# LPC1768HeaderBoardV1_0Sch.net
KiCad netlist of a schematic drawn in Altium Designer
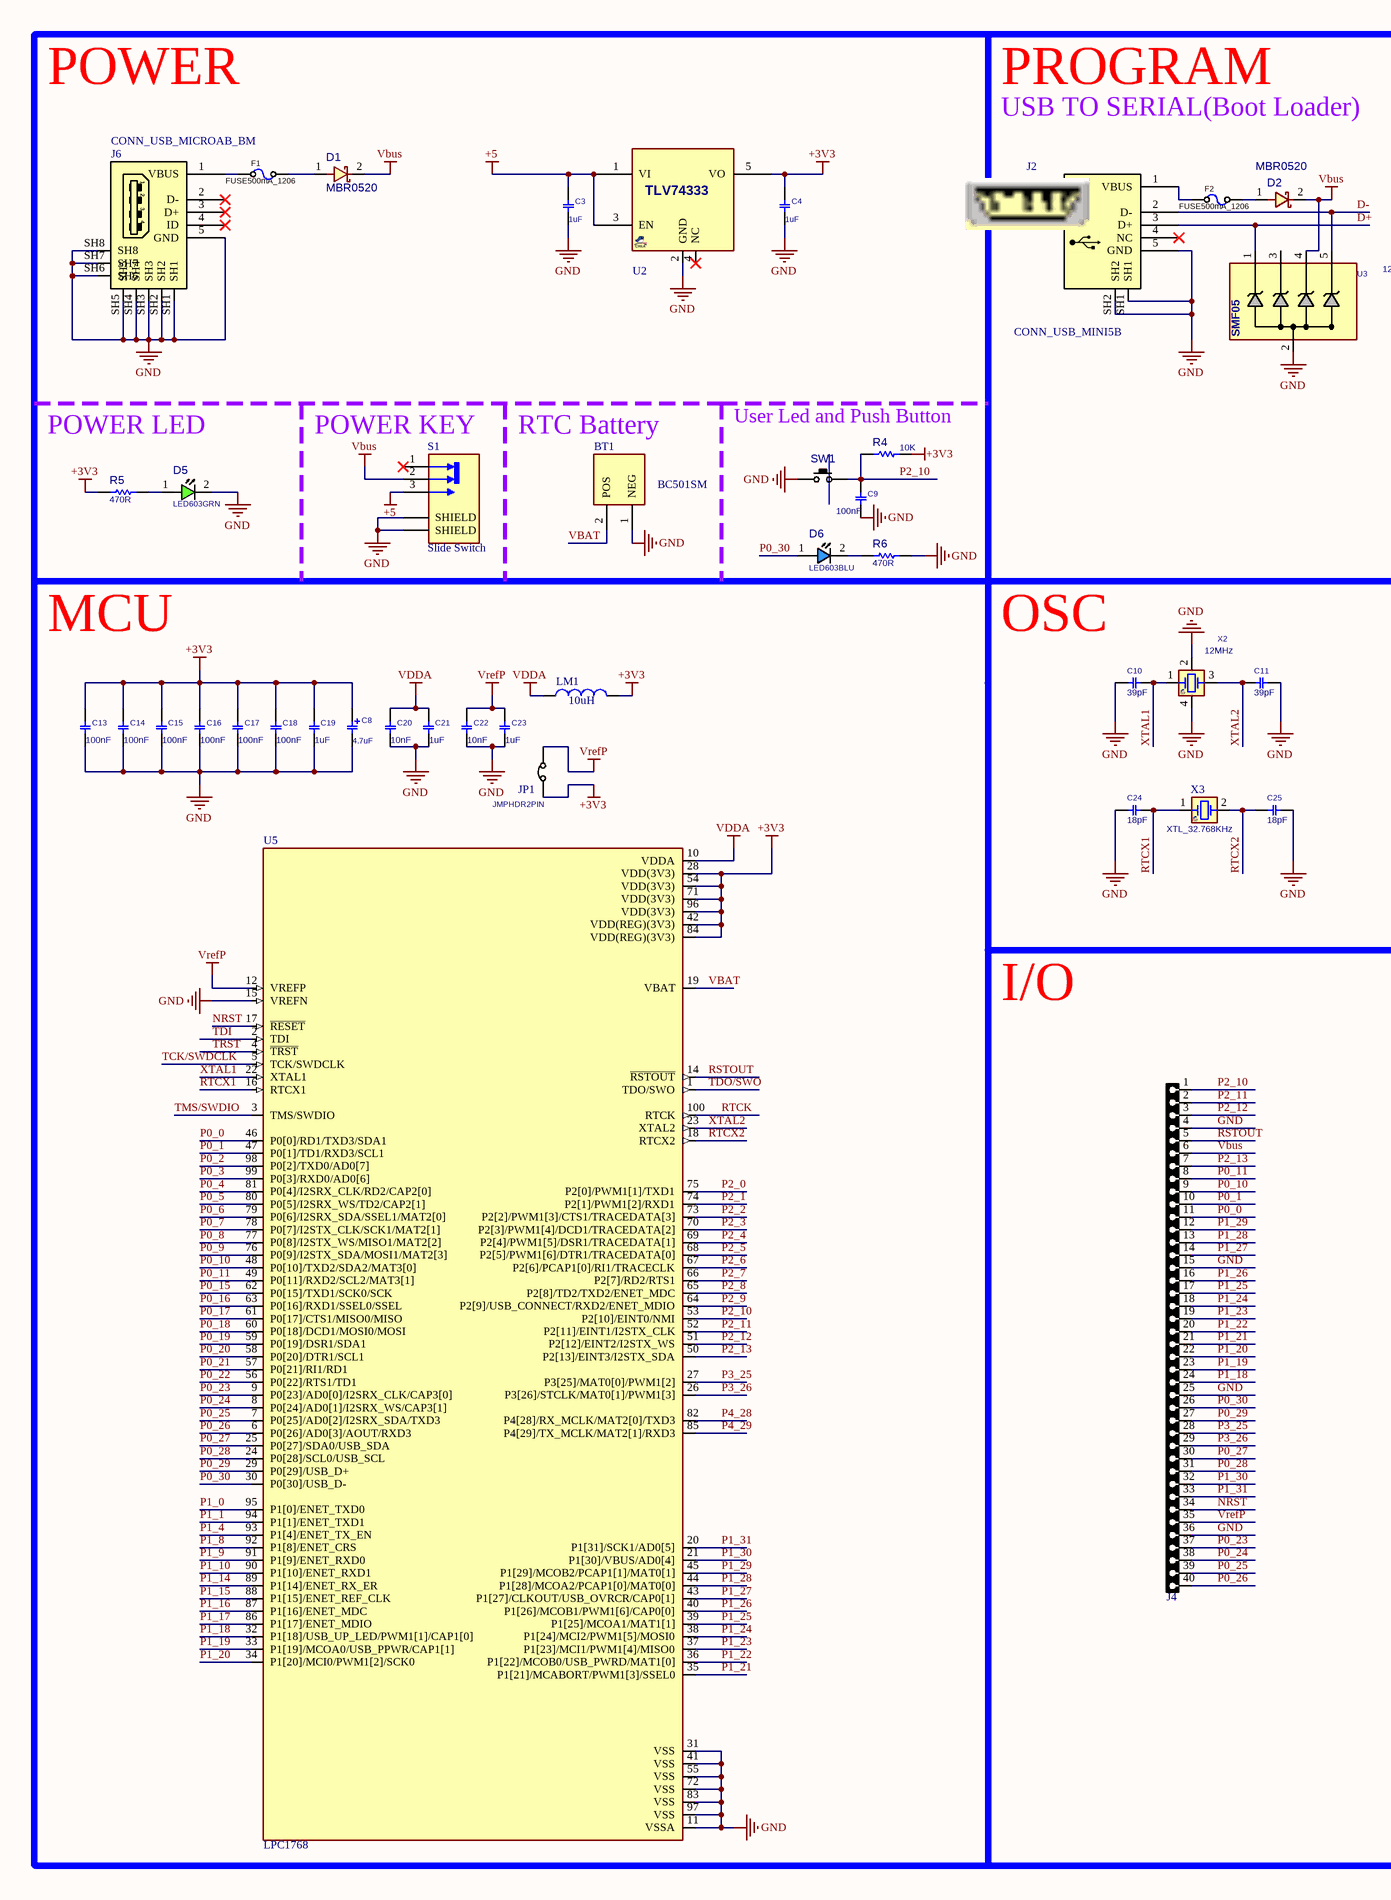
[diagram p0: LPC1768HeaderBoardV1.0Sch.SchDoc, left]
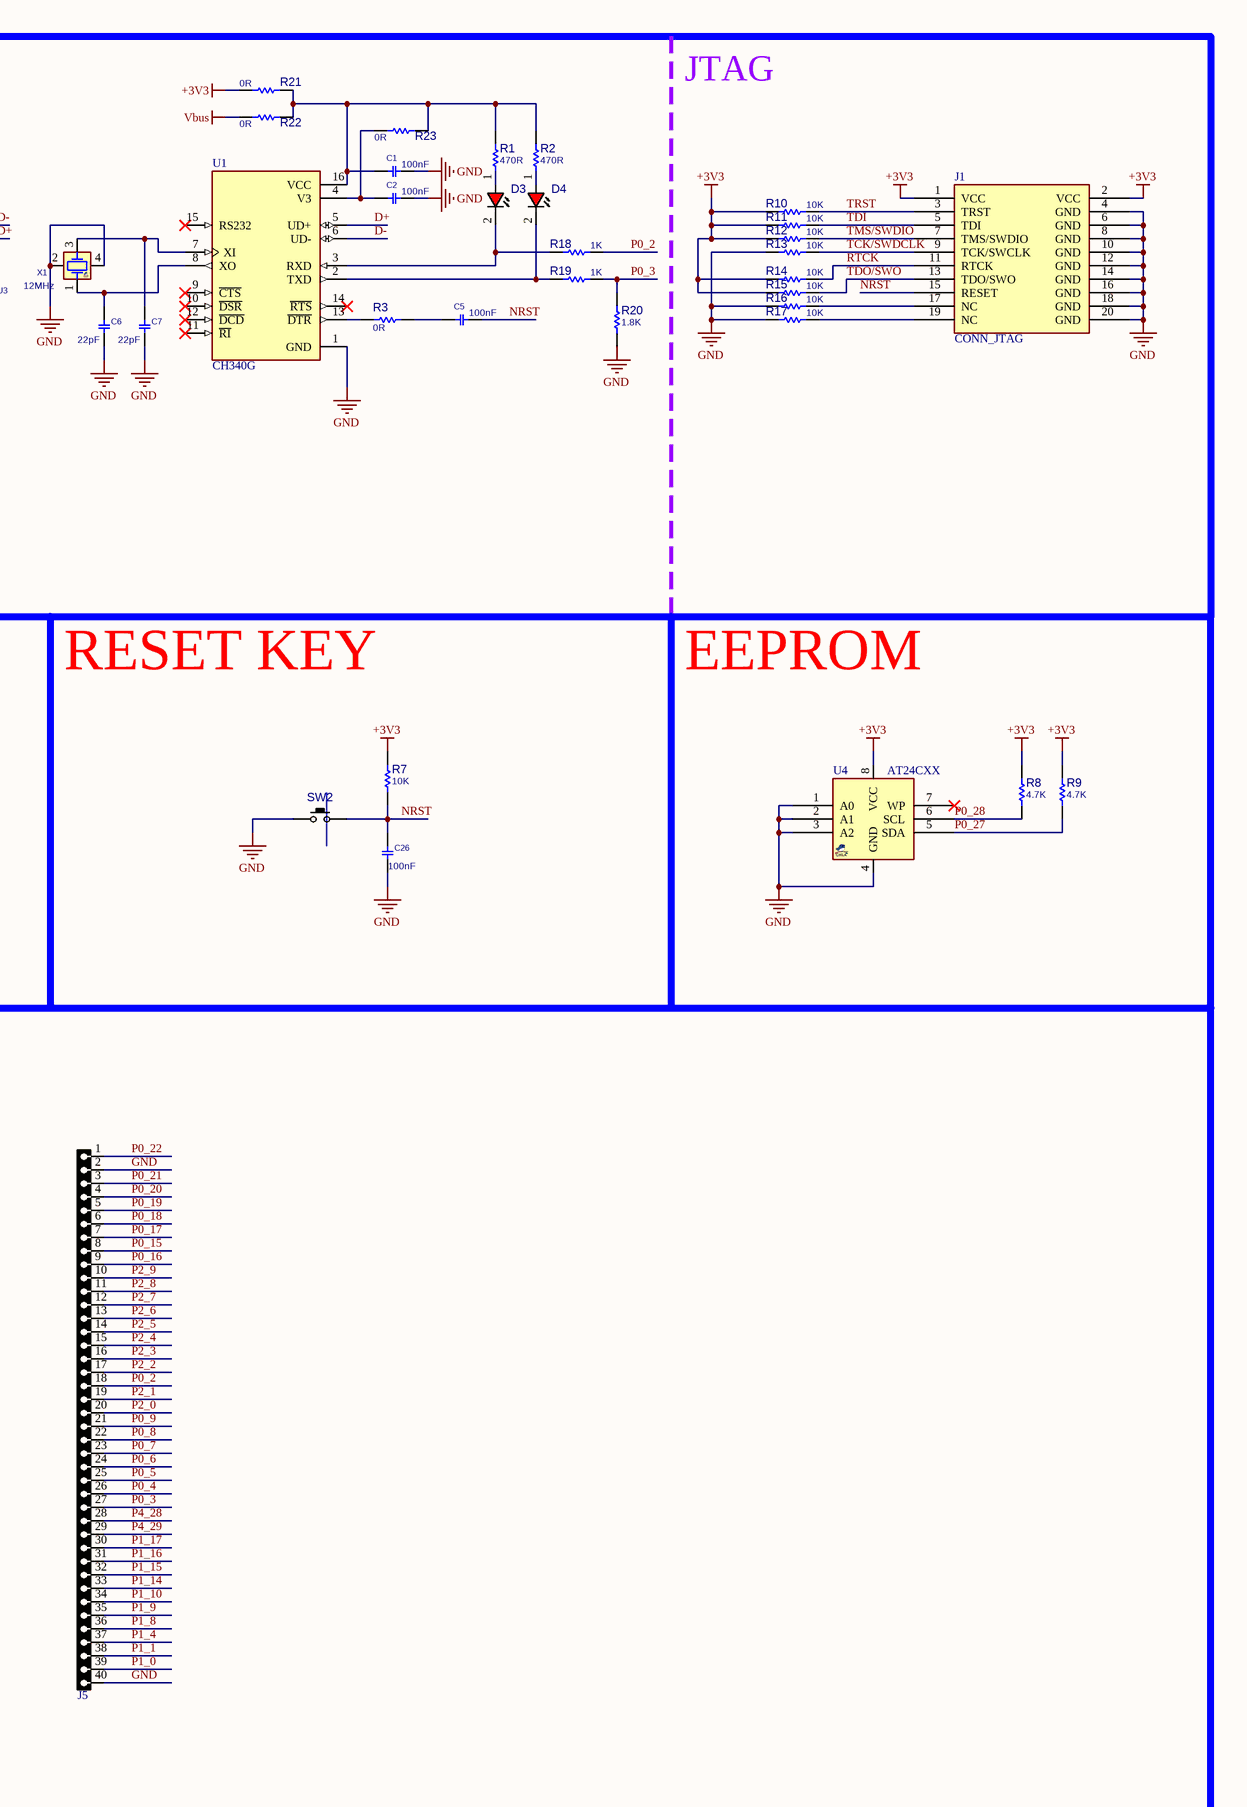
[diagram p1: LPC1768HeaderBoardV1.0Sch.SchDoc, right]

(export (version "E")
  (design (tool "Eeschema 10.0.6"))
  (components
    (comp (ref "BT1") (value "BC501SM") (footprint "BC501SM") (libsource (lib "Mehrdad") (part "BC501SM")))
    (comp (ref "C1")
      (value "100nF")
      (footprint "C0603")
      (description "CAP, MLCC")
      (fields (field (name "MANF_P#") "MANF_PART#"))
      (libsource (lib "passive_smd") (part "CAP_SMD_MLCC_0603"))
    )
    (comp (ref "C2")
      (value "100nF")
      (footprint "C0603")
      (description "CAP, MLCC")
      (fields (field (name "MANF_P#") "MANF_PART#"))
      (libsource (lib "passive_smd") (part "CAP_SMD_MLCC_0603"))
    )
    (comp (ref "C3")
      (value "1uF")
      (footprint "C0805")
      (description "CAP, MLCC, -F, -V, MATERIAL, -%, 0201")
      (fields (field (name "MANF_P#") "MANF_PART#"))
      (libsource (lib "passive_smd") (part "CAP_SMD_MLCC_0805"))
    )
    (comp (ref "C4")
      (value "1uF")
      (footprint "C0805")
      (description "CAP, MLCC, -F, -V, MATERIAL, -%, 0201")
      (fields (field (name "MANF_P#") "MANF_PART#"))
      (libsource (lib "passive_smd") (part "CAP_SMD_MLCC_0805"))
    )
    (comp (ref "C5")
      (value "100nF")
      (footprint "C0603")
      (description "CAP, MLCC")
      (fields (field (name "MANF_P#") "MANF_PART#"))
      (libsource (lib "passive_smd") (part "CAP_SMD_MLCC_0603"))
    )
    (comp (ref "C6")
      (value "22pF")
      (footprint "C0603")
      (description "CAP, MLCC")
      (fields (field (name "MANF_P#") "MANF_PART#"))
      (libsource (lib "passive_smd") (part "CAP_SMD_MLCC_0603"))
    )
    (comp (ref "C7")
      (value "22pF")
      (footprint "C0603")
      (description "CAP, MLCC")
      (fields (field (name "MANF_P#") "MANF_PART#"))
      (libsource (lib "passive_smd") (part "CAP_SMD_MLCC_0603"))
    )
    (comp (ref "C8")
      (value "4.7uF")
      (footprint "C_TN_3216")
      (description "CAP, SMD, TAN,")
      (libsource (lib "passive_smd") (part "CAP_SMD_TAN_3216"))
    )
    (comp (ref "C9")
      (value "100nF")
      (footprint "C0603")
      (description "CAP, MLCC")
      (fields (field (name "MANF_P#") "MANF_PART#"))
      (libsource (lib "passive_smd") (part "CAP_SMD_MLCC_0603"))
    )
    (comp (ref "C10")
      (value "39pF")
      (footprint "C0603")
      (description "CAP, MLCC")
      (fields (field (name "MANF_P#") "MANF_PART#"))
      (libsource (lib "passive_smd") (part "CAP_SMD_MLCC_0603"))
    )
    (comp (ref "C11")
      (value "39pF")
      (footprint "C0603")
      (description "CAP, MLCC")
      (fields (field (name "MANF_P#") "MANF_PART#"))
      (libsource (lib "passive_smd") (part "CAP_SMD_MLCC_0603"))
    )
    (comp (ref "C13")
      (value "100nF")
      (footprint "C0603")
      (description "CAP, MLCC")
      (fields (field (name "MANF_P#") "MANF_PART#"))
      (libsource (lib "passive_smd") (part "CAP_SMD_MLCC_0603"))
    )
    (comp (ref "C14")
      (value "100nF")
      (footprint "C0603")
      (description "CAP, MLCC")
      (fields (field (name "MANF_P#") "MANF_PART#"))
      (libsource (lib "passive_smd") (part "CAP_SMD_MLCC_0603"))
    )
    (comp (ref "C15")
      (value "100nF")
      (footprint "C0603")
      (description "CAP, MLCC")
      (fields (field (name "MANF_P#") "MANF_PART#"))
      (libsource (lib "passive_smd") (part "CAP_SMD_MLCC_0603"))
    )
    (comp (ref "C16")
      (value "100nF")
      (footprint "C0603")
      (description "CAP, MLCC")
      (fields (field (name "MANF_P#") "MANF_PART#"))
      (libsource (lib "passive_smd") (part "CAP_SMD_MLCC_0603"))
    )
    (comp (ref "C17")
      (value "100nF")
      (footprint "C0603")
      (description "CAP, MLCC")
      (fields (field (name "MANF_P#") "MANF_PART#"))
      (libsource (lib "passive_smd") (part "CAP_SMD_MLCC_0603"))
    )
    (comp (ref "C18")
      (value "100nF")
      (footprint "C0603")
      (description "CAP, MLCC")
      (fields (field (name "MANF_P#") "MANF_PART#"))
      (libsource (lib "passive_smd") (part "CAP_SMD_MLCC_0603"))
    )
    (comp (ref "C19")
      (value "1uF")
      (footprint "C0603")
      (description "CAP, MLCC")
      (fields (field (name "MANF_P#") "MANF_PART#"))
      (libsource (lib "passive_smd") (part "CAP_SMD_MLCC_0603"))
    )
    (comp (ref "C20")
      (value "10nF")
      (footprint "C0603")
      (description "CAP, MLCC")
      (fields (field (name "MANF_P#") "MANF_PART#"))
      (libsource (lib "passive_smd") (part "CAP_SMD_MLCC_0603"))
    )
    (comp (ref "C21")
      (value "1uF")
      (footprint "C0603")
      (description "CAP, MLCC")
      (fields (field (name "MANF_P#") "MANF_PART#"))
      (libsource (lib "passive_smd") (part "CAP_SMD_MLCC_0603"))
    )
    (comp (ref "C22")
      (value "10nF")
      (footprint "C0603")
      (description "CAP, MLCC")
      (fields (field (name "MANF_P#") "MANF_PART#"))
      (libsource (lib "passive_smd") (part "CAP_SMD_MLCC_0603"))
    )
    (comp (ref "C23")
      (value "1uF")
      (footprint "C0603")
      (description "CAP, MLCC")
      (fields (field (name "MANF_P#") "MANF_PART#"))
      (libsource (lib "passive_smd") (part "CAP_SMD_MLCC_0603"))
    )
    (comp (ref "C24")
      (value "18pF")
      (footprint "C0603")
      (description "CAP, MLCC")
      (fields (field (name "MANF_P#") "MANF_PART#"))
      (libsource (lib "passive_smd") (part "CAP_SMD_MLCC_0603"))
    )
    (comp (ref "C25")
      (value "18pF")
      (footprint "C0603")
      (description "CAP, MLCC")
      (fields (field (name "MANF_P#") "MANF_PART#"))
      (libsource (lib "passive_smd") (part "CAP_SMD_MLCC_0603"))
    )
    (comp (ref "C26")
      (value "100nF")
      (footprint "C0603")
      (description "CAP, MLCC")
      (fields (field (name "MANF_P#") "MANF_PART#"))
      (libsource (lib "passive_smd") (part "CAP_SMD_MLCC_0603"))
    )
    (comp (ref "D1")
      (value "MBR0520")
      (footprint "D_SOD123W")
      (description "DIODE, SCHOTTKY, 20V, 0.5A")
      (fields (field (name "MANF") "ON") (field (name "MANF_P#") "MBR0520LT1G"))
      (libsource (lib "diode") (part "DIODE_SMD_SCHOTTKY_MBR0520"))
    )
    (comp (ref "D2")
      (value "MBR0520")
      (footprint "D_SOD123W")
      (description "DIODE, SCHOTTKY, 20V, 0.5A")
      (fields (field (name "MANF") "ON") (field (name "MANF_P#") "MBR0520LT1G"))
      (libsource (lib "diode") (part "DIODE_SMD_SCHOTTKY_MBR0520"))
    )
    (comp (ref "D3")
      (value "~")
      (footprint "LED0603RED")
      (description "LED, SMD, 0603, RED")
      (fields (field (name "MANF") "MANF") (field (name "MANF_P#") "MANF_PART#"))
      (libsource (lib "led(diode)") (part "LED_SMD_0603_RED"))
    )
    (comp (ref "D4")
      (value "~")
      (footprint "LED0603RED")
      (description "LED, SMD, 0603, RED")
      (fields (field (name "MANF") "MANF") (field (name "MANF_P#") "MANF_PART#"))
      (libsource (lib "led(diode)") (part "LED_SMD_0603_RED"))
    )
    (comp (ref "D5")
      (value "LED603GRN")
      (footprint "LED0603GRN")
      (description "LED, SMD, 0603, GREEN")
      (fields (field (name "MANF") "Kingbright") (field (name "MANF_P#") "APT1608SGC"))
      (libsource (lib "led(diode)") (part "LED_SMD_0603_GRN"))
    )
    (comp (ref "D6")
      (value "LED603BLU")
      (footprint "LED0603BLU")
      (description "LED, SMD, 0603, BLUE")
      (fields (field (name "MANF") "MANF") (field (name "MANF_P#") "MANF_PART#"))
      (libsource (lib "led(diode)") (part "LED_SMD_0603_BLU"))
    )
    (comp (ref "F1")
      (value "FUSE500mA_1206")
      (footprint "F1206")
      (description "Fuse, 3A, 32VDC, 1206, SMD, Slow Blow")
      (fields (field (name "MANF") "Bourns") (field (name "MANF_P#") "SF-1206SP300-2"))
      (libsource (lib "protect_tvs_esd_fuse") (part "FUSE_3A_1206_SLOW"))
    )
    (comp (ref "F2")
      (value "FUSE500mA_1206")
      (footprint "F1206")
      (description "Fuse, 3A, 32VDC, 1206, SMD, Slow Blow")
      (fields (field (name "MANF") "Bourns") (field (name "MANF_P#") "SF-1206SP300-2"))
      (libsource (lib "protect_tvs_esd_fuse") (part "FUSE_3A_1206_SLOW"))
    )
    (comp (ref "J1")
      (value "CONN_JTAG")
      (footprint "IDC_2X10")
      (description "CONN, JTAG, ARM, 20P")
      (libsource (lib "conn_program") (part "CONN_JTAG_ARM_20"))
    )
    (comp (ref "J2")
      (value "CONN_USB_MINI5B")
      (footprint "USB_MINI_B5_SMD")
      (description "CONN, USB, MINI 5 B, R/A, SMD")
      (fields (field (name "MANF_P#") "UX60-MB-5ST") (field (name "MANF") "Hirose"))
      (libsource (lib "conn_usb") (part "CONN_USB_MINI5B_SMD"))
    )
    (comp (ref "J4")
      (value "HDRF40")
      (footprint "HDR_F_1X40")
      (description "CONN, HEADER, Female, pitch: 2.54mm, 40POS")
      (libsource (lib "conn_header_2.54_st") (part "HDR_F_1X40"))
    )
    (comp (ref "J5")
      (value "HDRF40")
      (footprint "HDR_F_1X40")
      (description "CONN, HEADER, Female, pitch: 2.54mm, 40POS")
      (libsource (lib "conn_header_2.54_st") (part "HDR_F_1X40"))
    )
    (comp (ref "J6")
      (value "CONN_USB_MICROAB_BM")
      (footprint "USB_MICRO_AB_BM_SHT")
      (description "CONN, USB, MICRO AB, R/A, SMD, BOTTOM MOUNT")
      (fields (field (name "MANF_P#") "47589-0001") (field (name "MANF") "MOLEX"))
      (libsource (lib "conn_usb") (part "CONN_USB_MICRO_AB_BM_SHT"))
    )
    (comp (ref "JP1")
      (value "JMPHDR2PIN")
      (footprint "JP_2_BLK")
      (description "JUMPER, HEADER 2PIN")
      (fields (field (name "MANF") "MANF") (field (name "MANF_P#") "MANF_P#"))
      (libsource (lib "test-tp_jumper") (part "JUMPER_HDR_2P"))
    )
    (comp (ref "LM1")
      (value "10uH")
      (footprint "0805L")
      (description "Inductor")
      (fields (field (name "PUBLISHER") "Altium Limited"))
      (libsource (lib "2017AbbasBasereh9365731239 -ver1") (part "L SMA 0.25W"))
    )
    (comp (ref "R1")
      (value "470R")
      (footprint "R0603")
      (description "RESISTOR, SMD")
      (libsource (lib "passive_smd") (part "RES_SMD_0603"))
    )
    (comp (ref "R2")
      (value "470R")
      (footprint "R0603")
      (description "RESISTOR, SMD")
      (libsource (lib "passive_smd") (part "RES_SMD_0603"))
    )
    (comp (ref "R3")
      (value "0R")
      (footprint "R0603")
      (description "RESISTOR, SMD")
      (libsource (lib "passive_smd") (part "RES_SMD_0603"))
    )
    (comp (ref "R4")
      (value "10K")
      (footprint "R0603")
      (description "RESISTOR, SMD")
      (libsource (lib "passive_smd") (part "RES_SMD_0603"))
    )
    (comp (ref "R5")
      (value "470R")
      (footprint "R0603")
      (description "RESISTOR, SMD")
      (libsource (lib "passive_smd") (part "RES_SMD_0603"))
    )
    (comp (ref "R6")
      (value "470R")
      (footprint "R0603")
      (description "RESISTOR, SMD")
      (libsource (lib "passive_smd") (part "RES_SMD_0603"))
    )
    (comp (ref "R7")
      (value "10K")
      (footprint "R0603")
      (description "RESISTOR, SMD")
      (libsource (lib "passive_smd") (part "RES_SMD_0603"))
    )
    (comp (ref "R8")
      (value "4.7K")
      (footprint "R0603")
      (description "RESISTOR, SMD")
      (libsource (lib "passive_smd") (part "RES_SMD_0603"))
    )
    (comp (ref "R9")
      (value "4.7K")
      (footprint "R0603")
      (description "RESISTOR, SMD")
      (libsource (lib "passive_smd") (part "RES_SMD_0603"))
    )
    (comp (ref "R10")
      (value "10K")
      (footprint "R0603")
      (description "RESISTOR, SMD")
      (libsource (lib "passive_smd") (part "RES_SMD_0603"))
    )
    (comp (ref "R11")
      (value "10K")
      (footprint "R0603")
      (description "RESISTOR, SMD")
      (libsource (lib "passive_smd") (part "RES_SMD_0603"))
    )
    (comp (ref "R12")
      (value "10K")
      (footprint "R0603")
      (description "RESISTOR, SMD")
      (libsource (lib "passive_smd") (part "RES_SMD_0603"))
    )
    (comp (ref "R13")
      (value "10K")
      (footprint "R0603")
      (description "RESISTOR, SMD")
      (libsource (lib "passive_smd") (part "RES_SMD_0603"))
    )
    (comp (ref "R14")
      (value "10K")
      (footprint "R0603")
      (description "RESISTOR, SMD")
      (libsource (lib "passive_smd") (part "RES_SMD_0603"))
    )
    (comp (ref "R15")
      (value "10K")
      (footprint "R0603")
      (description "RESISTOR, SMD")
      (libsource (lib "passive_smd") (part "RES_SMD_0603"))
    )
    (comp (ref "R16")
      (value "10K")
      (footprint "R0603")
      (description "RESISTOR, SMD")
      (libsource (lib "passive_smd") (part "RES_SMD_0603"))
    )
    (comp (ref "R17")
      (value "10K")
      (footprint "R0603")
      (description "RESISTOR, SMD")
      (libsource (lib "passive_smd") (part "RES_SMD_0603"))
    )
    (comp (ref "R18")
      (value "1K")
      (footprint "R0603")
      (description "RESISTOR, SMD")
      (libsource (lib "passive_smd") (part "RES_SMD_0603"))
    )
    (comp (ref "R19")
      (value "1K")
      (footprint "R0603")
      (description "RESISTOR, SMD")
      (libsource (lib "passive_smd") (part "RES_SMD_0603"))
    )
    (comp (ref "R20")
      (value "1.8K")
      (footprint "R0603")
      (description "RESISTOR, SMD")
      (libsource (lib "passive_smd") (part "RES_SMD_0603"))
    )
    (comp (ref "R21")
      (value "0R")
      (footprint "R0603")
      (description "RESISTOR, SMD")
      (libsource (lib "passive_smd") (part "RES_SMD_0603"))
    )
    (comp (ref "R22")
      (value "0R")
      (footprint "R0603")
      (description "RESISTOR, SMD")
      (libsource (lib "passive_smd") (part "RES_SMD_0603"))
    )
    (comp (ref "R23")
      (value "0R")
      (footprint "R0603")
      (description "RESISTOR, SMD")
      (libsource (lib "passive_smd") (part "RES_SMD_0603"))
    )
    (comp (ref "S1")
      (value "Slide Switch")
      (footprint "Slide Switch")
      (description "Push Slide Switch")
      (libsource (lib "Mehrdad") (part "Slide Switch"))
    )
    (comp (ref "SW1")
      (value "PUSHBUTTON")
      (footprint "SWPBS_SPST_6X3X5")
      (description "SWITCH, PUSH BUTTON, TACTILE, SMD, SPST, 6X3.5X5mm")
      (fields (field (name "MANF") "CTS") (field (name "MANF_P#") "222BMVBAR"))
      (libsource (lib "switch_tact_PUSHB") (part "SWPBS_SPST_6X3_222BMVBAR"))
    )
    (comp (ref "SW2")
      (value "PUSHBUTTON")
      (footprint "SWPBS_SPST_6X3X5")
      (description "SWITCH, PUSH BUTTON, TACTILE, SMD, SPST, 6X3.5X5mm")
      (fields (field (name "MANF") "CTS") (field (name "MANF_P#") "222BMVBAR"))
      (libsource (lib "switch_tact_PUSHB") (part "SWPBS_SPST_6X3_222BMVBAR"))
    )
    (comp (ref "U1")
      (value "CH340G")
      (footprint "CH340G")
      (description "USB Interface Integrated Circuit")
      (libsource (lib "Mehrdad") (part "CH340G"))
    )
    (comp (ref "U2")
      (value "TLV74333")
      (footprint "SOT23_5")
      (description "REG, Linear, LDO0.12V, Fixed, 300mA, VIN1.4~5.5V, VOUT1~5.5V, SOT-23-5")
      (fields (field (name "MANF") "Texas Instruments") (field (name "MANF_P#") "TLV74333PDQN"))
      (libsource (lib "pwr_reg_linear_LDO_highPSRR") (part "VREG_TLV74333_SOT23"))
    )
    (comp (ref "U3")
      (value "TVS_SMF05")
      (footprint "SOT353_5")
      (description "TVS, ESD PROTECT, 4CH, 5VRWM, 15KV")
      (fields (field (name "MANF_P#") "SMF05") (field (name "MANF") "Semtech"))
      (libsource (lib "protect_tvs_esd_fuse") (part "TVS_X4_SMF05"))
    )
    (comp (ref "U4")
      (value "AT24CXX")
      (footprint "SO_8")
      (description "EEPROM, I2C,")
      (libsource (lib "memory_eeprom_I2C") (part "EEPROM_I2C_AT24CXX_SOP8"))
    )
    (comp (ref "U5")
      (value "LPC1768")
      (footprint "LPC1768FBD100")
      (description "ARM Cortex-M3 512KB Flash , 64KB SRAM LQFP-100 , 100MHZ")
      (libsource (lib "Mehrdad") (part "LPC1768FBD100"))
    )
    (comp (ref "X1")
      (value "12MHz")
      (footprint "XTL_4_3225")
      (description "Crystal 12MHz")
      (fields (field (name "MANF") "ECS") (field (name "MANF_P#") "ECS-120-18-33-JEM-TR"))
      (libsource (lib "crystal") (part "XTL_4_12MHz_3225"))
    )
    (comp (ref "X2")
      (value "12MHz")
      (footprint "XTL_4_3225")
      (description "Crystal 12MHz")
      (fields (field (name "MANF") "ECS") (field (name "MANF_P#") "ECS-120-18-33-JEM-TR"))
      (libsource (lib "") (part "XTL_4_12MHz_3225_1"))
    )
    (comp (ref "X3")
      (value "XTL_32.768KHz")
      (footprint "XTL_2_3215")
      (description "Crystal, 32.768KHz, 3pF, 20PPM")
      (fields (field (name "MANF") "ABRACON") (field (name "MANF_P#") "ABS07W-32.768kHz-D-2-T"))
      (libsource (lib "crystal") (part "XTL_2_32.768_3215A"))
    )
  )
  (nets
    (net (code "1") (name "+3V3") (class "Default")
      (node (ref "C13") (pin "1") (pinfunction "1_1") (pintype "passive"))
      (node (ref "C14") (pin "1") (pinfunction "1_1") (pintype "passive"))
      (node (ref "C15") (pin "1") (pinfunction "1_1") (pintype "passive"))
      (node (ref "C16") (pin "1") (pinfunction "1_1") (pintype "passive"))
      (node (ref "C17") (pin "1") (pinfunction "1_1") (pintype "passive"))
      (node (ref "C18") (pin "1") (pinfunction "1_1") (pintype "passive"))
      (node (ref "C19") (pin "1") (pinfunction "1_1") (pintype "passive"))
      (node (ref "C4") (pin "2") (pinfunction "2_2") (pintype "passive"))
      (node (ref "C8") (pin "1") (pinfunction "1_1") (pintype "passive"))
      (node (ref "J1") (pin "1") (pinfunction "VCC_1") (pintype "passive"))
      (node (ref "J1") (pin "2") (pinfunction "VCC_2") (pintype "passive"))
      (node (ref "JP1") (pin "1") (pinfunction "1_1") (pintype "passive"))
      (node (ref "LM1") (pin "2") (pinfunction "2_2") (pintype "passive"))
      (node (ref "R10") (pin "2") (pinfunction "2_2") (pintype "passive"))
      (node (ref "R11") (pin "2") (pinfunction "2_2") (pintype "passive"))
      (node (ref "R12") (pin "2") (pinfunction "2_2") (pintype "passive"))
      (node (ref "R14") (pin "2") (pinfunction "2_2") (pintype "passive"))
      (node (ref "R15") (pin "2") (pinfunction "2_2") (pintype "passive"))
      (node (ref "R21") (pin "2") (pinfunction "2_2") (pintype "passive"))
      (node (ref "R4") (pin "1") (pinfunction "1_1") (pintype "passive"))
      (node (ref "R5") (pin "2") (pinfunction "2_2") (pintype "passive"))
      (node (ref "R7") (pin "2") (pinfunction "2_2") (pintype "passive"))
      (node (ref "R8") (pin "1") (pinfunction "1_1") (pintype "passive"))
      (node (ref "R9") (pin "1") (pinfunction "1_1") (pintype "passive"))
      (node (ref "U2") (pin "5") (pinfunction "VO_5") (pintype "passive"))
      (node (ref "U4") (pin "8") (pinfunction "VCC_8") (pintype "passive"))
      (node (ref "U5") (pin "28") (pinfunction "VDD(3V3)_28") (pintype "power_in"))
      (node (ref "U5") (pin "42") (pinfunction "VDD(REG)(3V3)_42") (pintype "power_in"))
      (node (ref "U5") (pin "54") (pinfunction "VDD(3V3)_54") (pintype "power_in"))
      (node (ref "U5") (pin "71") (pinfunction "VDD(3V3)_71") (pintype "power_in"))
      (node (ref "U5") (pin "84") (pinfunction "VDD(REG)(3V3)_84") (pintype "power_in"))
      (node (ref "U5") (pin "96") (pinfunction "VDD(3V3)_96") (pintype "power_in"))
    )
    (net (code "2") (name "+5") (class "Default")
      (node (ref "C3") (pin "2") (pinfunction "2_2") (pintype "passive"))
      (node (ref "S1") (pin "3") (pinfunction "3_3") (pintype "passive"))
      (node (ref "U2") (pin "1") (pinfunction "VI_1") (pintype "passive"))
      (node (ref "U2") (pin "3") (pinfunction "EN_3") (pintype "passive"))
    )
    (net (code "3") (name "/D+") (class "Default")
      (node (ref "J2") (pin "3") (pinfunction "D+_3") (pintype "passive"))
      (node (ref "U1") (pin "5") (pinfunction "UD+_5") (pintype "bidirectional"))
      (node (ref "U3") (pin "1") (pinfunction "1_1") (pintype "passive"))
    )
    (net (code "4") (name "/D-") (class "Default")
      (node (ref "J2") (pin "2") (pinfunction "D-_2") (pintype "passive"))
      (node (ref "U1") (pin "6") (pinfunction "UD-_6") (pintype "bidirectional"))
      (node (ref "U3") (pin "5") (pinfunction "5_5") (pintype "passive"))
    )
    (net (code "5") (name "/NRST") (class "Default")
      (node (ref "C26") (pin "1") (pinfunction "1_1") (pintype "passive"))
      (node (ref "C5") (pin "2") (pinfunction "2_2") (pintype "passive"))
      (node (ref "J1") (pin "15") (pinfunction "RESET_15") (pintype "passive"))
      (node (ref "J4") (pin "34") (pinfunction "34_34") (pintype "passive"))
      (node (ref "R7") (pin "1") (pinfunction "1_1") (pintype "passive"))
      (node (ref "SW2") (pin "2") (pinfunction "P3_2") (pintype "passive"))
      (node (ref "U5") (pin "17") (pinfunction "~{RESET}_17") (pintype "input"))
    )
    (net (code "6") (name "/P0_0") (class "Default")
      (node (ref "J4") (pin "11") (pinfunction "11_11") (pintype "passive"))
      (node (ref "U5") (pin "46") (pinfunction "P0[0]/RD1/TXD3/SDA1_46") (pintype "bidirectional"))
    )
    (net (code "7") (name "/P0_1") (class "Default")
      (node (ref "J4") (pin "10") (pinfunction "10_10") (pintype "passive"))
      (node (ref "U5") (pin "47") (pinfunction "P0[1]/TD1/RXD3/SCL1_47") (pintype "bidirectional"))
    )
    (net (code "8") (name "/P0_2") (class "Default")
      (node (ref "J5") (pin "18") (pinfunction "18_18") (pintype "passive"))
      (node (ref "R18") (pin "1") (pinfunction "1_1") (pintype "passive"))
      (node (ref "U5") (pin "98") (pinfunction "P0[2]/TXD0/AD0[7]_98") (pintype "bidirectional"))
    )
    (net (code "9") (name "/P0_3") (class "Default")
      (node (ref "J5") (pin "27") (pinfunction "27_27") (pintype "passive"))
      (node (ref "R19") (pin "1") (pinfunction "1_1") (pintype "passive"))
      (node (ref "R20") (pin "1") (pinfunction "1_1") (pintype "passive"))
      (node (ref "U5") (pin "99") (pinfunction "P0[3]/RXD0/AD0[6]_99") (pintype "bidirectional"))
    )
    (net (code "10") (name "/P0_4") (class "Default")
      (node (ref "J5") (pin "26") (pinfunction "26_26") (pintype "passive"))
      (node (ref "U5") (pin "81") (pinfunction "P0[4]/I2SRX_CLK/RD2/CAP2[0]_81") (pintype "bidirectional"))
    )
    (net (code "11") (name "/P0_5") (class "Default")
      (node (ref "J5") (pin "25") (pinfunction "25_25") (pintype "passive"))
      (node (ref "U5") (pin "80") (pinfunction "P0[5]/I2SRX_WS/TD2/CAP2[1]_80") (pintype "bidirectional"))
    )
    (net (code "12") (name "/P0_6") (class "Default")
      (node (ref "J5") (pin "24") (pinfunction "24_24") (pintype "passive"))
      (node (ref "U5") (pin "79") (pinfunction "P0[6]/I2SRX_SDA/SSEL1/MAT2[0]_79") (pintype "bidirectional"))
    )
    (net (code "13") (name "/P0_7") (class "Default")
      (node (ref "J5") (pin "23") (pinfunction "23_23") (pintype "passive"))
      (node (ref "U5") (pin "78") (pinfunction "P0[7]/I2STX_CLK/SCK1/MAT2[1]_78") (pintype "bidirectional"))
    )
    (net (code "14") (name "/P0_8") (class "Default")
      (node (ref "J5") (pin "22") (pinfunction "22_22") (pintype "passive"))
      (node (ref "U5") (pin "77") (pinfunction "P0[8]/I2STX_WS/MISO1/MAT2[2]_77") (pintype "bidirectional"))
    )
    (net (code "15") (name "/P0_9") (class "Default")
      (node (ref "J5") (pin "21") (pinfunction "21_21") (pintype "passive"))
      (node (ref "U5") (pin "76") (pinfunction "P0[9]/I2STX_SDA/MOSI1/MAT2[3]_76") (pintype "bidirectional"))
    )
    (net (code "16") (name "/P0_10") (class "Default")
      (node (ref "J4") (pin "9") (pinfunction "9_9") (pintype "passive"))
      (node (ref "U5") (pin "48") (pinfunction "P0[10]/TXD2/SDA2/MAT3[0]_48") (pintype "bidirectional"))
    )
    (net (code "17") (name "/P0_11") (class "Default")
      (node (ref "J4") (pin "8") (pinfunction "8_8") (pintype "passive"))
      (node (ref "U5") (pin "49") (pinfunction "P0[11]/RXD2/SCL2/MAT3[1]_49") (pintype "bidirectional"))
    )
    (net (code "18") (name "/P0_15") (class "Default")
      (node (ref "J5") (pin "8") (pinfunction "8_8") (pintype "passive"))
      (node (ref "U5") (pin "62") (pinfunction "P0[15]/TXD1/SCK0/SCK_62") (pintype "bidirectional"))
    )
    (net (code "19") (name "/P0_16") (class "Default")
      (node (ref "J5") (pin "9") (pinfunction "9_9") (pintype "passive"))
      (node (ref "U5") (pin "63") (pinfunction "P0[16]/RXD1/SSEL0/SSEL_63") (pintype "bidirectional"))
    )
    (net (code "20") (name "/P0_17") (class "Default")
      (node (ref "J5") (pin "7") (pinfunction "7_7") (pintype "passive"))
      (node (ref "U5") (pin "61") (pinfunction "P0[17]/CTS1/MISO0/MISO_61") (pintype "bidirectional"))
    )
    (net (code "21") (name "/P0_18") (class "Default")
      (node (ref "J5") (pin "6") (pinfunction "6_6") (pintype "passive"))
      (node (ref "U5") (pin "60") (pinfunction "P0[18]/DCD1/MOSI0/MOSI_60") (pintype "bidirectional"))
    )
    (net (code "22") (name "/P0_19") (class "Default")
      (node (ref "J5") (pin "5") (pinfunction "5_5") (pintype "passive"))
      (node (ref "U5") (pin "59") (pinfunction "P0[19]/DSR1/SDA1_59") (pintype "bidirectional"))
    )
    (net (code "23") (name "/P0_20") (class "Default")
      (node (ref "J5") (pin "4") (pinfunction "4_4") (pintype "passive"))
      (node (ref "U5") (pin "58") (pinfunction "P0[20]/DTR1/SCL1_58") (pintype "bidirectional"))
    )
    (net (code "24") (name "/P0_21") (class "Default")
      (node (ref "J5") (pin "3") (pinfunction "3_3") (pintype "passive"))
      (node (ref "U5") (pin "57") (pinfunction "P0[21]/RI1/RD1_57") (pintype "bidirectional"))
    )
    (net (code "25") (name "/P0_22") (class "Default")
      (node (ref "J5") (pin "1") (pinfunction "1_1") (pintype "passive"))
      (node (ref "U5") (pin "56") (pinfunction "P0[22]/RTS1/TD1_56") (pintype "bidirectional"))
    )
    (net (code "26") (name "/P0_23") (class "Default")
      (node (ref "J4") (pin "37") (pinfunction "37_37") (pintype "passive"))
      (node (ref "U5") (pin "9") (pinfunction "P0[23]/AD0[0]/I2SRX_CLK/CAP3[0]_9") (pintype "bidirectional"))
    )
    (net (code "27") (name "/P0_24") (class "Default")
      (node (ref "J4") (pin "38") (pinfunction "38_38") (pintype "passive"))
      (node (ref "U5") (pin "8") (pinfunction "P0[24]/AD0[1]/I2SRX_WS/CAP3[1]_8") (pintype "bidirectional"))
    )
    (net (code "28") (name "/P0_25") (class "Default")
      (node (ref "J4") (pin "39") (pinfunction "39_39") (pintype "passive"))
      (node (ref "U5") (pin "7") (pinfunction "P0[25]/AD0[2]/I2SRX_SDA/TXD3_7") (pintype "bidirectional"))
    )
    (net (code "29") (name "/P0_26") (class "Default")
      (node (ref "J4") (pin "40") (pinfunction "40_40") (pintype "passive"))
      (node (ref "U5") (pin "6") (pinfunction "P0[26]/AD0[3]/AOUT/RXD3_6") (pintype "bidirectional"))
    )
    (net (code "30") (name "/P0_27") (class "Default")
      (node (ref "J4") (pin "30") (pinfunction "30_30") (pintype "passive"))
      (node (ref "R9") (pin "2") (pinfunction "2_2") (pintype "passive"))
      (node (ref "U4") (pin "5") (pinfunction "SDA_5") (pintype "passive"))
      (node (ref "U5") (pin "25") (pinfunction "P0[27]/SDA0/USB_SDA_25") (pintype "bidirectional"))
    )
    (net (code "31") (name "/P0_28") (class "Default")
      (node (ref "J4") (pin "31") (pinfunction "31_31") (pintype "passive"))
      (node (ref "R8") (pin "2") (pinfunction "2_2") (pintype "passive"))
      (node (ref "U4") (pin "6") (pinfunction "SCL_6") (pintype "passive"))
      (node (ref "U5") (pin "24") (pinfunction "P0[28]/SCL0/USB_SCL_24") (pintype "bidirectional"))
    )
    (net (code "32") (name "/P0_29") (class "Default")
      (node (ref "J4") (pin "27") (pinfunction "27_27") (pintype "passive"))
      (node (ref "U5") (pin "29") (pinfunction "P0[29]/USB_D+_29") (pintype "bidirectional"))
    )
    (net (code "33") (name "/P0_30") (class "Default")
      (node (ref "D6") (pin "1") (pinfunction "ANODE_1") (pintype "passive"))
      (node (ref "J4") (pin "26") (pinfunction "26_26") (pintype "passive"))
      (node (ref "U5") (pin "30") (pinfunction "P0[30]/USB_D-_30") (pintype "bidirectional"))
    )
    (net (code "34") (name "/P1_0") (class "Default")
      (node (ref "J5") (pin "39") (pinfunction "39_39") (pintype "passive"))
      (node (ref "U5") (pin "95") (pinfunction "P1[0]/ENET_TXD0_95") (pintype "bidirectional"))
    )
    (net (code "35") (name "/P1_1") (class "Default")
      (node (ref "J5") (pin "38") (pinfunction "38_38") (pintype "passive"))
      (node (ref "U5") (pin "94") (pinfunction "P1[1]/ENET_TXD1_94") (pintype "bidirectional"))
    )
    (net (code "36") (name "/P1_4") (class "Default")
      (node (ref "J5") (pin "37") (pinfunction "37_37") (pintype "passive"))
      (node (ref "U5") (pin "93") (pinfunction "P1[4]/ENET_TX_EN_93") (pintype "bidirectional"))
    )
    (net (code "37") (name "/P1_8") (class "Default")
      (node (ref "J5") (pin "36") (pinfunction "36_36") (pintype "passive"))
      (node (ref "U5") (pin "92") (pinfunction "P1[8]/ENET_CRS_92") (pintype "bidirectional"))
    )
    (net (code "38") (name "/P1_9") (class "Default")
      (node (ref "J5") (pin "35") (pinfunction "35_35") (pintype "passive"))
      (node (ref "U5") (pin "91") (pinfunction "P1[9]/ENET_RXD0_91") (pintype "bidirectional"))
    )
    (net (code "39") (name "/P1_10") (class "Default")
      (node (ref "J5") (pin "34") (pinfunction "34_34") (pintype "passive"))
      (node (ref "U5") (pin "90") (pinfunction "P1[10]/ENET_RXD1_90") (pintype "bidirectional"))
    )
    (net (code "40") (name "/P1_14") (class "Default")
      (node (ref "J5") (pin "33") (pinfunction "33_33") (pintype "passive"))
      (node (ref "U5") (pin "89") (pinfunction "P1[14]/ENET_RX_ER_89") (pintype "bidirectional"))
    )
    (net (code "41") (name "/P1_15") (class "Default")
      (node (ref "J5") (pin "32") (pinfunction "32_32") (pintype "passive"))
      (node (ref "U5") (pin "88") (pinfunction "P1[15]/ENET_REF_CLK_88") (pintype "bidirectional"))
    )
    (net (code "42") (name "/P1_16") (class "Default")
      (node (ref "J5") (pin "31") (pinfunction "31_31") (pintype "passive"))
      (node (ref "U5") (pin "87") (pinfunction "P1[16]/ENET_MDC_87") (pintype "bidirectional"))
    )
    (net (code "43") (name "/P1_17") (class "Default")
      (node (ref "J5") (pin "30") (pinfunction "30_30") (pintype "passive"))
      (node (ref "U5") (pin "86") (pinfunction "P1[17]/ENET_MDIO_86") (pintype "bidirectional"))
    )
    (net (code "44") (name "/P1_18") (class "Default")
      (node (ref "J4") (pin "24") (pinfunction "24_24") (pintype "passive"))
      (node (ref "U5") (pin "32") (pinfunction "P1[18]/USB_UP_LED/PWM1[1]/CAP1[0]_32") (pintype "bidirectional"))
    )
    (net (code "45") (name "/P1_19") (class "Default")
      (node (ref "J4") (pin "23") (pinfunction "23_23") (pintype "passive"))
      (node (ref "U5") (pin "33") (pinfunction "P1[19]/MCOA0/USB_PPWR/CAP1[1]_33") (pintype "bidirectional"))
    )
    (net (code "46") (name "/P1_20") (class "Default")
      (node (ref "J4") (pin "22") (pinfunction "22_22") (pintype "passive"))
      (node (ref "U5") (pin "34") (pinfunction "P1[20]/MCI0/PWM1[2]/SCK0_34") (pintype "bidirectional"))
    )
    (net (code "47") (name "/P1_21") (class "Default")
      (node (ref "J4") (pin "21") (pinfunction "21_21") (pintype "passive"))
      (node (ref "U5") (pin "35") (pinfunction "P1[21]/MCABORT/PWM1[3]/SSEL0_35") (pintype "bidirectional"))
    )
    (net (code "48") (name "/P1_22") (class "Default")
      (node (ref "J4") (pin "20") (pinfunction "20_20") (pintype "passive"))
      (node (ref "U5") (pin "36") (pinfunction "P1[22]/MCOB0/USB_PWRD/MAT1[0]_36") (pintype "bidirectional"))
    )
    (net (code "49") (name "/P1_23") (class "Default")
      (node (ref "J4") (pin "19") (pinfunction "19_19") (pintype "passive"))
      (node (ref "U5") (pin "37") (pinfunction "P1[23]/MCI1/PWM1[4]/MISO0_37") (pintype "bidirectional"))
    )
    (net (code "50") (name "/P1_24") (class "Default")
      (node (ref "J4") (pin "18") (pinfunction "18_18") (pintype "passive"))
      (node (ref "U5") (pin "38") (pinfunction "P1[24]/MCI2/PWM1[5]/MOSI0_38") (pintype "bidirectional"))
    )
    (net (code "51") (name "/P1_25") (class "Default")
      (node (ref "J4") (pin "17") (pinfunction "17_17") (pintype "passive"))
      (node (ref "U5") (pin "39") (pinfunction "P1[25]/MCOA1/MAT1[1]_39") (pintype "bidirectional"))
    )
    (net (code "52") (name "/P1_26") (class "Default")
      (node (ref "J4") (pin "16") (pinfunction "16_16") (pintype "passive"))
      (node (ref "U5") (pin "40") (pinfunction "P1[26]/MCOB1/PWM1[6]/CAP0[0]_40") (pintype "bidirectional"))
    )
    (net (code "53") (name "/P1_27") (class "Default")
      (node (ref "J4") (pin "14") (pinfunction "14_14") (pintype "passive"))
      (node (ref "U5") (pin "43") (pinfunction "P1[27]/CLKOUT/USB_OVRCR/CAP0[1]_43") (pintype "bidirectional"))
    )
    (net (code "54") (name "/P1_28") (class "Default")
      (node (ref "J4") (pin "13") (pinfunction "13_13") (pintype "passive"))
      (node (ref "U5") (pin "44") (pinfunction "P1[28]/MCOA2/PCAP1[0]/MAT0[0]_44") (pintype "bidirectional"))
    )
    (net (code "55") (name "/P1_29") (class "Default")
      (node (ref "J4") (pin "12") (pinfunction "12_12") (pintype "passive"))
      (node (ref "U5") (pin "45") (pinfunction "P1[29]/MCOB2/PCAP1[1]/MAT0[1]_45") (pintype "bidirectional"))
    )
    (net (code "56") (name "/P1_30") (class "Default")
      (node (ref "J4") (pin "32") (pinfunction "32_32") (pintype "passive"))
      (node (ref "U5") (pin "21") (pinfunction "P1[30]/VBUS/AD0[4]_21") (pintype "bidirectional"))
    )
    (net (code "57") (name "/P1_31") (class "Default")
      (node (ref "J4") (pin "33") (pinfunction "33_33") (pintype "passive"))
      (node (ref "U5") (pin "20") (pinfunction "P1[31]/SCK1/AD0[5]_20") (pintype "bidirectional"))
    )
    (net (code "58") (name "/P2_0") (class "Default")
      (node (ref "J5") (pin "20") (pinfunction "20_20") (pintype "passive"))
      (node (ref "U5") (pin "75") (pinfunction "P2[0]/PWM1[1]/TXD1_75") (pintype "bidirectional"))
    )
    (net (code "59") (name "/P2_1") (class "Default")
      (node (ref "J5") (pin "19") (pinfunction "19_19") (pintype "passive"))
      (node (ref "U5") (pin "74") (pinfunction "P2[1]/PWM1[2]/RXD1_74") (pintype "bidirectional"))
    )
    (net (code "60") (name "/P2_2") (class "Default")
      (node (ref "J5") (pin "17") (pinfunction "17_17") (pintype "passive"))
      (node (ref "U5") (pin "73") (pinfunction "P2[2]/PWM1[3]/CTS1/TRACEDATA[3]_73") (pintype "bidirectional"))
    )
    (net (code "61") (name "/P2_3") (class "Default")
      (node (ref "J5") (pin "16") (pinfunction "16_16") (pintype "passive"))
      (node (ref "U5") (pin "70") (pinfunction "P2[3]/PWM1[4]/DCD1/TRACEDATA[2]_70") (pintype "bidirectional"))
    )
    (net (code "62") (name "/P2_4") (class "Default")
      (node (ref "J5") (pin "15") (pinfunction "15_15") (pintype "passive"))
      (node (ref "U5") (pin "69") (pinfunction "P2[4]/PWM1[5]/DSR1/TRACEDATA[1]_69") (pintype "bidirectional"))
    )
    (net (code "63") (name "/P2_5") (class "Default")
      (node (ref "J5") (pin "14") (pinfunction "14_14") (pintype "passive"))
      (node (ref "U5") (pin "68") (pinfunction "P2[5]/PWM1[6]/DTR1/TRACEDATA[0]_68") (pintype "bidirectional"))
    )
    (net (code "64") (name "/P2_6") (class "Default")
      (node (ref "J5") (pin "13") (pinfunction "13_13") (pintype "passive"))
      (node (ref "U5") (pin "67") (pinfunction "P2[6]/PCAP1[0]/RI1/TRACECLK_67") (pintype "bidirectional"))
    )
    (net (code "65") (name "/P2_7") (class "Default")
      (node (ref "J5") (pin "12") (pinfunction "12_12") (pintype "passive"))
      (node (ref "U5") (pin "66") (pinfunction "P2[7]/RD2/RTS1_66") (pintype "bidirectional"))
    )
    (net (code "66") (name "/P2_8") (class "Default")
      (node (ref "J5") (pin "11") (pinfunction "11_11") (pintype "passive"))
      (node (ref "U5") (pin "65") (pinfunction "P2[8]/TD2/TXD2/ENET_MDC_65") (pintype "bidirectional"))
    )
    (net (code "67") (name "/P2_9") (class "Default")
      (node (ref "J5") (pin "10") (pinfunction "10_10") (pintype "passive"))
      (node (ref "U5") (pin "64") (pinfunction "P2[9]/USB_CONNECT/RXD2/ENET_MDIO_64") (pintype "bidirectional"))
    )
    (net (code "68") (name "/P2_10") (class "Default")
      (node (ref "C9") (pin "1") (pinfunction "1_1") (pintype "passive"))
      (node (ref "J4") (pin "1") (pinfunction "1_1") (pintype "passive"))
      (node (ref "R4") (pin "2") (pinfunction "2_2") (pintype "passive"))
      (node (ref "SW1") (pin "2") (pinfunction "P3_2") (pintype "passive"))
      (node (ref "U5") (pin "53") (pinfunction "P2[10]/EINT0/NMI_53") (pintype "bidirectional"))
    )
    (net (code "69") (name "/P2_11") (class "Default")
      (node (ref "J4") (pin "2") (pinfunction "2_2") (pintype "passive"))
      (node (ref "U5") (pin "52") (pinfunction "P2[11]/EINT1/I2STX_CLK_52") (pintype "bidirectional"))
    )
    (net (code "70") (name "/P2_12") (class "Default")
      (node (ref "J4") (pin "3") (pinfunction "3_3") (pintype "passive"))
      (node (ref "U5") (pin "51") (pinfunction "P2[12]/EINT2/I2STX_WS_51") (pintype "bidirectional"))
    )
    (net (code "71") (name "/P2_13") (class "Default")
      (node (ref "J4") (pin "7") (pinfunction "7_7") (pintype "passive"))
      (node (ref "U5") (pin "50") (pinfunction "P2[13]/EINT3/I2STX_SDA_50") (pintype "bidirectional"))
    )
    (net (code "72") (name "/P3_25") (class "Default")
      (node (ref "J4") (pin "28") (pinfunction "28_28") (pintype "passive"))
      (node (ref "U5") (pin "27") (pinfunction "P3[25]/MAT0[0]/PWM1[2]_27") (pintype "bidirectional"))
    )
    (net (code "73") (name "/P3_26") (class "Default")
      (node (ref "J4") (pin "29") (pinfunction "29_29") (pintype "passive"))
      (node (ref "U5") (pin "26") (pinfunction "P3[26]/STCLK/MAT0[1]/PWM1[3]_26") (pintype "bidirectional"))
    )
    (net (code "74") (name "/P4_28") (class "Default")
      (node (ref "J5") (pin "28") (pinfunction "28_28") (pintype "passive"))
      (node (ref "U5") (pin "82") (pinfunction "P4[28]/RX_MCLK/MAT2[0]/TXD3_82") (pintype "bidirectional"))
    )
    (net (code "75") (name "/P4_29") (class "Default")
      (node (ref "J5") (pin "29") (pinfunction "29_29") (pintype "passive"))
      (node (ref "U5") (pin "85") (pinfunction "P4[29]/TX_MCLK/MAT2[1]/RXD3_85") (pintype "bidirectional"))
    )
    (net (code "76") (name "/RSTOUT") (class "Default")
      (node (ref "J4") (pin "5") (pinfunction "5_5") (pintype "passive"))
      (node (ref "U5") (pin "14") (pinfunction "~{RSTOUT}_14") (pintype "output"))
    )
    (net (code "77") (name "/RTCK") (class "Default")
      (node (ref "J1") (pin "11") (pinfunction "RTCK_11") (pintype "passive"))
      (node (ref "R14") (pin "1") (pinfunction "1_1") (pintype "passive"))
      (node (ref "U5") (pin "100") (pinfunction "RTCK_100") (pintype "output"))
    )
    (net (code "78") (name "/RTCX1") (class "Default")
      (node (ref "C24") (pin "1") (pinfunction "1_1") (pintype "passive"))
      (node (ref "U5") (pin "16") (pinfunction "RTCX1_16") (pintype "input"))
      (node (ref "X3") (pin "1") (pinfunction "OSC1_1") (pintype "passive"))
    )
    (net (code "79") (name "/RTCX2") (class "Default")
      (node (ref "C25") (pin "2") (pinfunction "2_2") (pintype "passive"))
      (node (ref "U5") (pin "18") (pinfunction "RTCX2_18") (pintype "output"))
      (node (ref "X3") (pin "2") (pinfunction "OSC2_2") (pintype "passive"))
    )
    (net (code "80") (name "/TCK{slash}SWDCLK") (class "Default")
      (node (ref "J1") (pin "9") (pinfunction "TCK/SWCLK_9") (pintype "passive"))
      (node (ref "R13") (pin "1") (pinfunction "1_1") (pintype "passive"))
      (node (ref "U5") (pin "5") (pinfunction "TCK/SWDCLK_5") (pintype "input"))
    )
    (net (code "81") (name "/TDI") (class "Default")
      (node (ref "J1") (pin "5") (pinfunction "TDI_5") (pintype "passive"))
      (node (ref "R11") (pin "1") (pinfunction "1_1") (pintype "passive"))
      (node (ref "U5") (pin "2") (pinfunction "TDI_2") (pintype "input"))
    )
    (net (code "82") (name "/TDO{slash}SWO") (class "Default")
      (node (ref "J1") (pin "13") (pinfunction "TDO/SWO_13") (pintype "passive"))
      (node (ref "R15") (pin "1") (pinfunction "1_1") (pintype "passive"))
      (node (ref "U5") (pin "1") (pinfunction "TDO/SWO_1") (pintype "output"))
    )
    (net (code "83") (name "/TMS{slash}SWDIO") (class "Default")
      (node (ref "J1") (pin "7") (pinfunction "TMS/SWDIO_7") (pintype "passive"))
      (node (ref "R12") (pin "1") (pinfunction "1_1") (pintype "passive"))
      (node (ref "U5") (pin "3") (pinfunction "TMS/SWDIO_3") (pintype "bidirectional"))
    )
    (net (code "84") (name "/TRST") (class "Default")
      (node (ref "J1") (pin "3") (pinfunction "TRST_3") (pintype "passive"))
      (node (ref "R10") (pin "1") (pinfunction "1_1") (pintype "passive"))
      (node (ref "U5") (pin "4") (pinfunction "~{TRST}_4") (pintype "input"))
    )
    (net (code "85") (name "/VBAT") (class "Default")
      (node (ref "BT1") (pin "2") (pinfunction "POS_2") (pintype "passive"))
      (node (ref "U5") (pin "19") (pinfunction "VBAT_19") (pintype "power_in"))
    )
    (net (code "86") (name "/XTAL1") (class "Default")
      (node (ref "C10") (pin "1") (pinfunction "1_1") (pintype "passive"))
      (node (ref "U5") (pin "22") (pinfunction "XTAL1_22") (pintype "input"))
      (node (ref "X2") (pin "1") (pinfunction "1_1") (pintype "passive"))
    )
    (net (code "87") (name "/XTAL2") (class "Default")
      (node (ref "C11") (pin "2") (pinfunction "2_2") (pintype "passive"))
      (node (ref "U5") (pin "23") (pinfunction "XTAL2_23") (pintype "output"))
      (node (ref "X2") (pin "3") (pinfunction "2_3") (pintype "passive"))
    )
    (net (code "88") (name "GND") (class "Default")
      (node (ref "BT1") (pin "1") (pinfunction "NEG_1") (pintype "passive"))
      (node (ref "C1") (pin "2") (pinfunction "2_2") (pintype "passive"))
      (node (ref "C10") (pin "2") (pinfunction "2_2") (pintype "passive"))
      (node (ref "C11") (pin "1") (pinfunction "1_1") (pintype "passive"))
      (node (ref "C13") (pin "2") (pinfunction "2_2") (pintype "passive"))
      (node (ref "C14") (pin "2") (pinfunction "2_2") (pintype "passive"))
      (node (ref "C15") (pin "2") (pinfunction "2_2") (pintype "passive"))
      (node (ref "C16") (pin "2") (pinfunction "2_2") (pintype "passive"))
      (node (ref "C17") (pin "2") (pinfunction "2_2") (pintype "passive"))
      (node (ref "C18") (pin "2") (pinfunction "2_2") (pintype "passive"))
      (node (ref "C19") (pin "2") (pinfunction "2_2") (pintype "passive"))
      (node (ref "C2") (pin "2") (pinfunction "2_2") (pintype "passive"))
      (node (ref "C20") (pin "2") (pinfunction "2_2") (pintype "passive"))
      (node (ref "C21") (pin "2") (pinfunction "2_2") (pintype "passive"))
      (node (ref "C22") (pin "2") (pinfunction "2_2") (pintype "passive"))
      (node (ref "C23") (pin "2") (pinfunction "2_2") (pintype "passive"))
      (node (ref "C24") (pin "2") (pinfunction "2_2") (pintype "passive"))
      (node (ref "C25") (pin "1") (pinfunction "1_1") (pintype "passive"))
      (node (ref "C26") (pin "2") (pinfunction "2_2") (pintype "passive"))
      (node (ref "C3") (pin "1") (pinfunction "1_1") (pintype "passive"))
      (node (ref "C4") (pin "1") (pinfunction "1_1") (pintype "passive"))
      (node (ref "C6") (pin "2") (pinfunction "2_2") (pintype "passive"))
      (node (ref "C7") (pin "2") (pinfunction "2_2") (pintype "passive"))
      (node (ref "C8") (pin "2") (pinfunction "2_2") (pintype "passive"))
      (node (ref "C9") (pin "2") (pinfunction "2_2") (pintype "passive"))
      (node (ref "D5") (pin "2") (pinfunction "CATHODE_2") (pintype "passive"))
      (node (ref "J1") (pin "10") (pinfunction "GND_10") (pintype "passive"))
      (node (ref "J1") (pin "12") (pinfunction "GND_12") (pintype "passive"))
      (node (ref "J1") (pin "14") (pinfunction "GND_14") (pintype "passive"))
      (node (ref "J1") (pin "16") (pinfunction "GND_16") (pintype "passive"))
      (node (ref "J1") (pin "18") (pinfunction "GND_18") (pintype "passive"))
      (node (ref "J1") (pin "20") (pinfunction "GND_20") (pintype "passive"))
      (node (ref "J1") (pin "4") (pinfunction "GND_4") (pintype "passive"))
      (node (ref "J1") (pin "6") (pinfunction "GND_6") (pintype "passive"))
      (node (ref "J1") (pin "8") (pinfunction "GND_8") (pintype "passive"))
      (node (ref "J2") (pin "5") (pinfunction "GND_5") (pintype "power_in"))
      (node (ref "J2") (pin "SH1") (pinfunction "SH1_SH1") (pintype "passive"))
      (node (ref "J2") (pin "SH2") (pinfunction "SH2_SH2") (pintype "passive"))
      (node (ref "J4") (pin "15") (pinfunction "15_15") (pintype "passive"))
      (node (ref "J4") (pin "25") (pinfunction "25_25") (pintype "passive"))
      (node (ref "J4") (pin "36") (pinfunction "36_36") (pintype "passive"))
      (node (ref "J4") (pin "4") (pinfunction "4_4") (pintype "passive"))
      (node (ref "J5") (pin "2") (pinfunction "2_2") (pintype "passive"))
      (node (ref "J5") (pin "40") (pinfunction "40_40") (pintype "passive"))
      (node (ref "J6") (pin "5") (pinfunction "GND_5") (pintype "power_in"))
      (node (ref "J6") (pin "SH1") (pinfunction "SH1_SH1") (pintype "passive"))
      (node (ref "J6") (pin "SH2") (pinfunction "SH2_SH2") (pintype "passive"))
      (node (ref "J6") (pin "SH3") (pinfunction "SH3_SH3") (pintype "passive"))
      (node (ref "J6") (pin "SH4") (pinfunction "SH4_SH4") (pintype "passive"))
      (node (ref "J6") (pin "SH5") (pinfunction "SH5_SH5") (pintype "passive"))
      (node (ref "J6") (pin "SH6") (pinfunction "SH6_SH6") (pintype "passive"))
      (node (ref "J6") (pin "SH7") (pinfunction "SH7_SH7") (pintype "passive"))
      (node (ref "J6") (pin "SH8") (pinfunction "SH8_SH8") (pintype "passive"))
      (node (ref "R13") (pin "2") (pinfunction "2_2") (pintype "passive"))
      (node (ref "R16") (pin "2") (pinfunction "2_2") (pintype "passive"))
      (node (ref "R17") (pin "2") (pinfunction "2_2") (pintype "passive"))
      (node (ref "R20") (pin "2") (pinfunction "2_2") (pintype "passive"))
      (node (ref "R6") (pin "1") (pinfunction "1_1") (pintype "passive"))
      (node (ref "S1") (pin "S1") (pinfunction "SHIELD_S1") (pintype "passive"))
      (node (ref "S1") (pin "S2") (pinfunction "SHIELD_S2") (pintype "passive"))
      (node (ref "SW1") (pin "1") (pinfunction "P1_1") (pintype "passive"))
      (node (ref "SW2") (pin "1") (pinfunction "P1_1") (pintype "passive"))
      (node (ref "U1") (pin "1") (pinfunction "GND_1") (pintype "power_in"))
      (node (ref "U2") (pin "2") (pinfunction "GND_2") (pintype "passive"))
      (node (ref "U3") (pin "2") (pinfunction "2_2") (pintype "passive"))
      (node (ref "U4") (pin "1") (pinfunction "A0_1") (pintype "passive"))
      (node (ref "U4") (pin "2") (pinfunction "A1_2") (pintype "passive"))
      (node (ref "U4") (pin "3") (pinfunction "A2_3") (pintype "passive"))
      (node (ref "U4") (pin "4") (pinfunction "GND_4") (pintype "passive"))
      (node (ref "U5") (pin "11") (pinfunction "VSSA_11") (pintype "power_in"))
      (node (ref "U5") (pin "15") (pinfunction "VREFN_15") (pintype "input"))
      (node (ref "U5") (pin "31") (pinfunction "VSS_31") (pintype "power_in"))
      (node (ref "U5") (pin "41") (pinfunction "VSS_41") (pintype "power_in"))
      (node (ref "U5") (pin "55") (pinfunction "VSS_55") (pintype "power_in"))
      (node (ref "U5") (pin "72") (pinfunction "VSS_72") (pintype "power_in"))
      (node (ref "U5") (pin "83") (pinfunction "VSS_83") (pintype "power_in"))
      (node (ref "U5") (pin "97") (pinfunction "VSS_97") (pintype "power_in"))
      (node (ref "X1") (pin "2") (pinfunction "2_2") (pintype "passive"))
      (node (ref "X1") (pin "4") (pinfunction "4_4") (pintype "passive"))
      (node (ref "X2") (pin "2") (pinfunction "2_2") (pintype "passive"))
      (node (ref "X2") (pin "4") (pinfunction "4_4") (pintype "passive"))
    )
    (net (code "89") (name "Net-(C5-Pad1)") (class "Default")
      (node (ref "C5") (pin "1") (pinfunction "1_1") (pintype "passive"))
      (node (ref "R3") (pin "1") (pinfunction "1_1") (pintype "passive"))
    )
    (net (code "90") (name "Net-(D1-Pad1)") (class "Default")
      (node (ref "D1") (pin "1") (pinfunction "1_1") (pintype "passive"))
      (node (ref "F1") (pin "2") (pinfunction "2_2") (pintype "passive"))
    )
    (net (code "91") (name "Net-(D2-Pad1)") (class "Default")
      (node (ref "D2") (pin "1") (pinfunction "1_1") (pintype "passive"))
      (node (ref "F2") (pin "2") (pinfunction "2_2") (pintype "passive"))
    )
    (net (code "92") (name "Net-(D3-ANODE)") (class "Default")
      (node (ref "D3") (pin "1") (pinfunction "ANODE_1") (pintype "passive"))
      (node (ref "R1") (pin "2") (pinfunction "2_2") (pintype "passive"))
    )
    (net (code "93") (name "Net-(D3-CATHODE)") (class "Default")
      (node (ref "D3") (pin "2") (pinfunction "CATHODE_2") (pintype "passive"))
      (node (ref "R18") (pin "2") (pinfunction "2_2") (pintype "passive"))
      (node (ref "U1") (pin "3") (pinfunction "RXD_3") (pintype "input"))
    )
    (net (code "94") (name "Net-(D4-ANODE)") (class "Default")
      (node (ref "D4") (pin "1") (pinfunction "ANODE_1") (pintype "passive"))
      (node (ref "R2") (pin "2") (pinfunction "2_2") (pintype "passive"))
    )
    (net (code "95") (name "Net-(D4-CATHODE)") (class "Default")
      (node (ref "D4") (pin "2") (pinfunction "CATHODE_2") (pintype "passive"))
      (node (ref "R19") (pin "2") (pinfunction "2_2") (pintype "passive"))
      (node (ref "U1") (pin "2") (pinfunction "TXD_2") (pintype "output"))
    )
    (net (code "96") (name "Net-(D5-ANODE)") (class "Default")
      (node (ref "D5") (pin "1") (pinfunction "ANODE_1") (pintype "passive"))
      (node (ref "R5") (pin "1") (pinfunction "1_1") (pintype "passive"))
    )
    (net (code "97") (name "Net-(D6-CATHODE)") (class "Default")
      (node (ref "D6") (pin "2") (pinfunction "CATHODE_2") (pintype "passive"))
      (node (ref "R6") (pin "2") (pinfunction "2_2") (pintype "passive"))
    )
    (net (code "98") (name "Net-(J1-NC-Pad17)") (class "Default")
      (node (ref "J1") (pin "17") (pinfunction "NC_17") (pintype "passive"))
      (node (ref "R16") (pin "1") (pinfunction "1_1") (pintype "passive"))
    )
    (net (code "99") (name "Net-(J1-NC-Pad19)") (class "Default")
      (node (ref "J1") (pin "19") (pinfunction "NC_19") (pintype "passive"))
      (node (ref "R17") (pin "1") (pinfunction "1_1") (pintype "passive"))
    )
    (net (code "100") (name "Net-(J2-VBUS)") (class "Default")
      (node (ref "F2") (pin "1") (pinfunction "1_1") (pintype "passive"))
      (node (ref "J2") (pin "1") (pinfunction "VBUS_1") (pintype "power_in"))
    )
    (net (code "101") (name "Net-(J6-VBUS)") (class "Default")
      (node (ref "F1") (pin "1") (pinfunction "1_1") (pintype "passive"))
      (node (ref "J6") (pin "1") (pinfunction "VBUS_1") (pintype "power_in"))
    )
    (net (code "102") (name "Net-(U1-V3)") (class "Default")
      (node (ref "C2") (pin "1") (pinfunction "1_1") (pintype "passive"))
      (node (ref "R23") (pin "2") (pinfunction "2_2") (pintype "passive"))
      (node (ref "U1") (pin "4") (pinfunction "V3_4") (pintype "power_in"))
    )
    (net (code "103") (name "Net-(U1-VCC)") (class "Default")
      (node (ref "C1") (pin "1") (pinfunction "1_1") (pintype "passive"))
      (node (ref "R1") (pin "1") (pinfunction "1_1") (pintype "passive"))
      (node (ref "R2") (pin "1") (pinfunction "1_1") (pintype "passive"))
      (node (ref "R21") (pin "1") (pinfunction "1_1") (pintype "passive"))
      (node (ref "R22") (pin "1") (pinfunction "1_1") (pintype "passive"))
      (node (ref "R23") (pin "1") (pinfunction "1_1") (pintype "passive"))
      (node (ref "U1") (pin "16") (pinfunction "VCC_16") (pintype "power_in"))
    )
    (net (code "104") (name "Net-(U1-XI)") (class "Default")
      (node (ref "C7") (pin "1") (pinfunction "1_1") (pintype "passive"))
      (node (ref "U1") (pin "7") (pinfunction "XI_7") (pintype "input"))
      (node (ref "X1") (pin "3") (pinfunction "2_3") (pintype "passive"))
    )
    (net (code "105") (name "Net-(U1-XO)") (class "Default")
      (node (ref "C6") (pin "1") (pinfunction "1_1") (pintype "passive"))
      (node (ref "U1") (pin "8") (pinfunction "XO_8") (pintype "output"))
      (node (ref "X1") (pin "1") (pinfunction "1_1") (pintype "passive"))
    )
    (net (code "106") (name "Net-(U1-~{DTR})") (class "Default")
      (node (ref "R3") (pin "2") (pinfunction "2_2") (pintype "passive"))
      (node (ref "U1") (pin "13") (pinfunction "~{DTR}_13") (pintype "output"))
    )
    (net (code "107") (name "VDDA") (class "Default")
      (node (ref "C20") (pin "1") (pinfunction "1_1") (pintype "passive"))
      (node (ref "C21") (pin "1") (pinfunction "1_1") (pintype "passive"))
      (node (ref "LM1") (pin "1") (pinfunction "1_1") (pintype "passive"))
      (node (ref "U5") (pin "10") (pinfunction "VDDA_10") (pintype "power_in"))
    )
    (net (code "108") (name "Vbus") (class "Default")
      (node (ref "D1") (pin "2") (pinfunction "2_2") (pintype "passive"))
      (node (ref "D2") (pin "2") (pinfunction "2_2") (pintype "passive"))
      (node (ref "J4") (pin "6") (pinfunction "6_6") (pintype "passive"))
      (node (ref "R22") (pin "2") (pinfunction "2_2") (pintype "passive"))
      (node (ref "S1") (pin "2") (pinfunction "2_2") (pintype "passive"))
      (node (ref "U3") (pin "4") (pinfunction "4_4") (pintype "passive"))
    )
    (net (code "109") (name "VrefP") (class "Default")
      (node (ref "C22") (pin "1") (pinfunction "1_1") (pintype "passive"))
      (node (ref "C23") (pin "1") (pinfunction "1_1") (pintype "passive"))
      (node (ref "J4") (pin "35") (pinfunction "35_35") (pintype "passive"))
      (node (ref "JP1") (pin "2") (pinfunction "2_2") (pintype "passive"))
      (node (ref "U5") (pin "12") (pinfunction "VREFP_12") (pintype "input"))
    )
    (net (code "110") (name "unconnected-(J2-NC-Pad4)") (class "Default")
      (node (ref "J2") (pin "4") (pinfunction "NC_4") (pintype "power_in+no_connect"))
    )
    (net (code "111") (name "unconnected-(J6-D+-Pad3)") (class "Default")
      (node (ref "J6") (pin "3") (pinfunction "D+_3") (pintype "passive+no_connect"))
    )
    (net (code "112") (name "unconnected-(J6-D--Pad2)") (class "Default")
      (node (ref "J6") (pin "2") (pinfunction "D-_2") (pintype "passive+no_connect"))
    )
    (net (code "113") (name "unconnected-(J6-ID-Pad4)") (class "Default")
      (node (ref "J6") (pin "4") (pinfunction "ID_4") (pintype "power_in+no_connect"))
    )
    (net (code "114") (name "unconnected-(S1-Pad1)") (class "Default")
      (node (ref "S1") (pin "1") (pinfunction "1_1") (pintype "passive+no_connect"))
    )
    (net (code "115") (name "unconnected-(U1-RS232-Pad15)") (class "Default")
      (node (ref "U1") (pin "15") (pinfunction "RS232_15") (pintype "input+no_connect"))
    )
    (net (code "116") (name "unconnected-(U1-~{CTS}-Pad9)") (class "Default")
      (node (ref "U1") (pin "9") (pinfunction "~{CTS}_9") (pintype "input+no_connect"))
    )
    (net (code "117") (name "unconnected-(U1-~{DCD}-Pad12)") (class "Default")
      (node (ref "U1") (pin "12") (pinfunction "~{DCD}_12") (pintype "input+no_connect"))
    )
    (net (code "118") (name "unconnected-(U1-~{DSR}-Pad10)") (class "Default")
      (node (ref "U1") (pin "10") (pinfunction "~{DSR}_10") (pintype "input+no_connect"))
    )
    (net (code "119") (name "unconnected-(U1-~{RI}-Pad11)") (class "Default")
      (node (ref "U1") (pin "11") (pinfunction "~{RI}_11") (pintype "input+no_connect"))
    )
    (net (code "120") (name "unconnected-(U1-~{RTS}-Pad14)") (class "Default")
      (node (ref "U1") (pin "14") (pinfunction "~{RTS}_14") (pintype "output+no_connect"))
    )
    (net (code "121") (name "unconnected-(U2-NC-Pad4)") (class "Default")
      (node (ref "U2") (pin "4") (pinfunction "NC_4") (pintype "passive+no_connect"))
    )
    (net (code "122") (name "unconnected-(U3-Pad3)") (class "Default")
      (node (ref "U3") (pin "3") (pinfunction "3_3") (pintype "passive"))
    )
    (net (code "123") (name "unconnected-(U4-WP-Pad7)") (class "Default")
      (node (ref "U4") (pin "7") (pinfunction "WP_7") (pintype "passive+no_connect"))
    )
  )
)
